# 7_VGA.net
KiCad netlist of a schematic drawn in Altium Designer
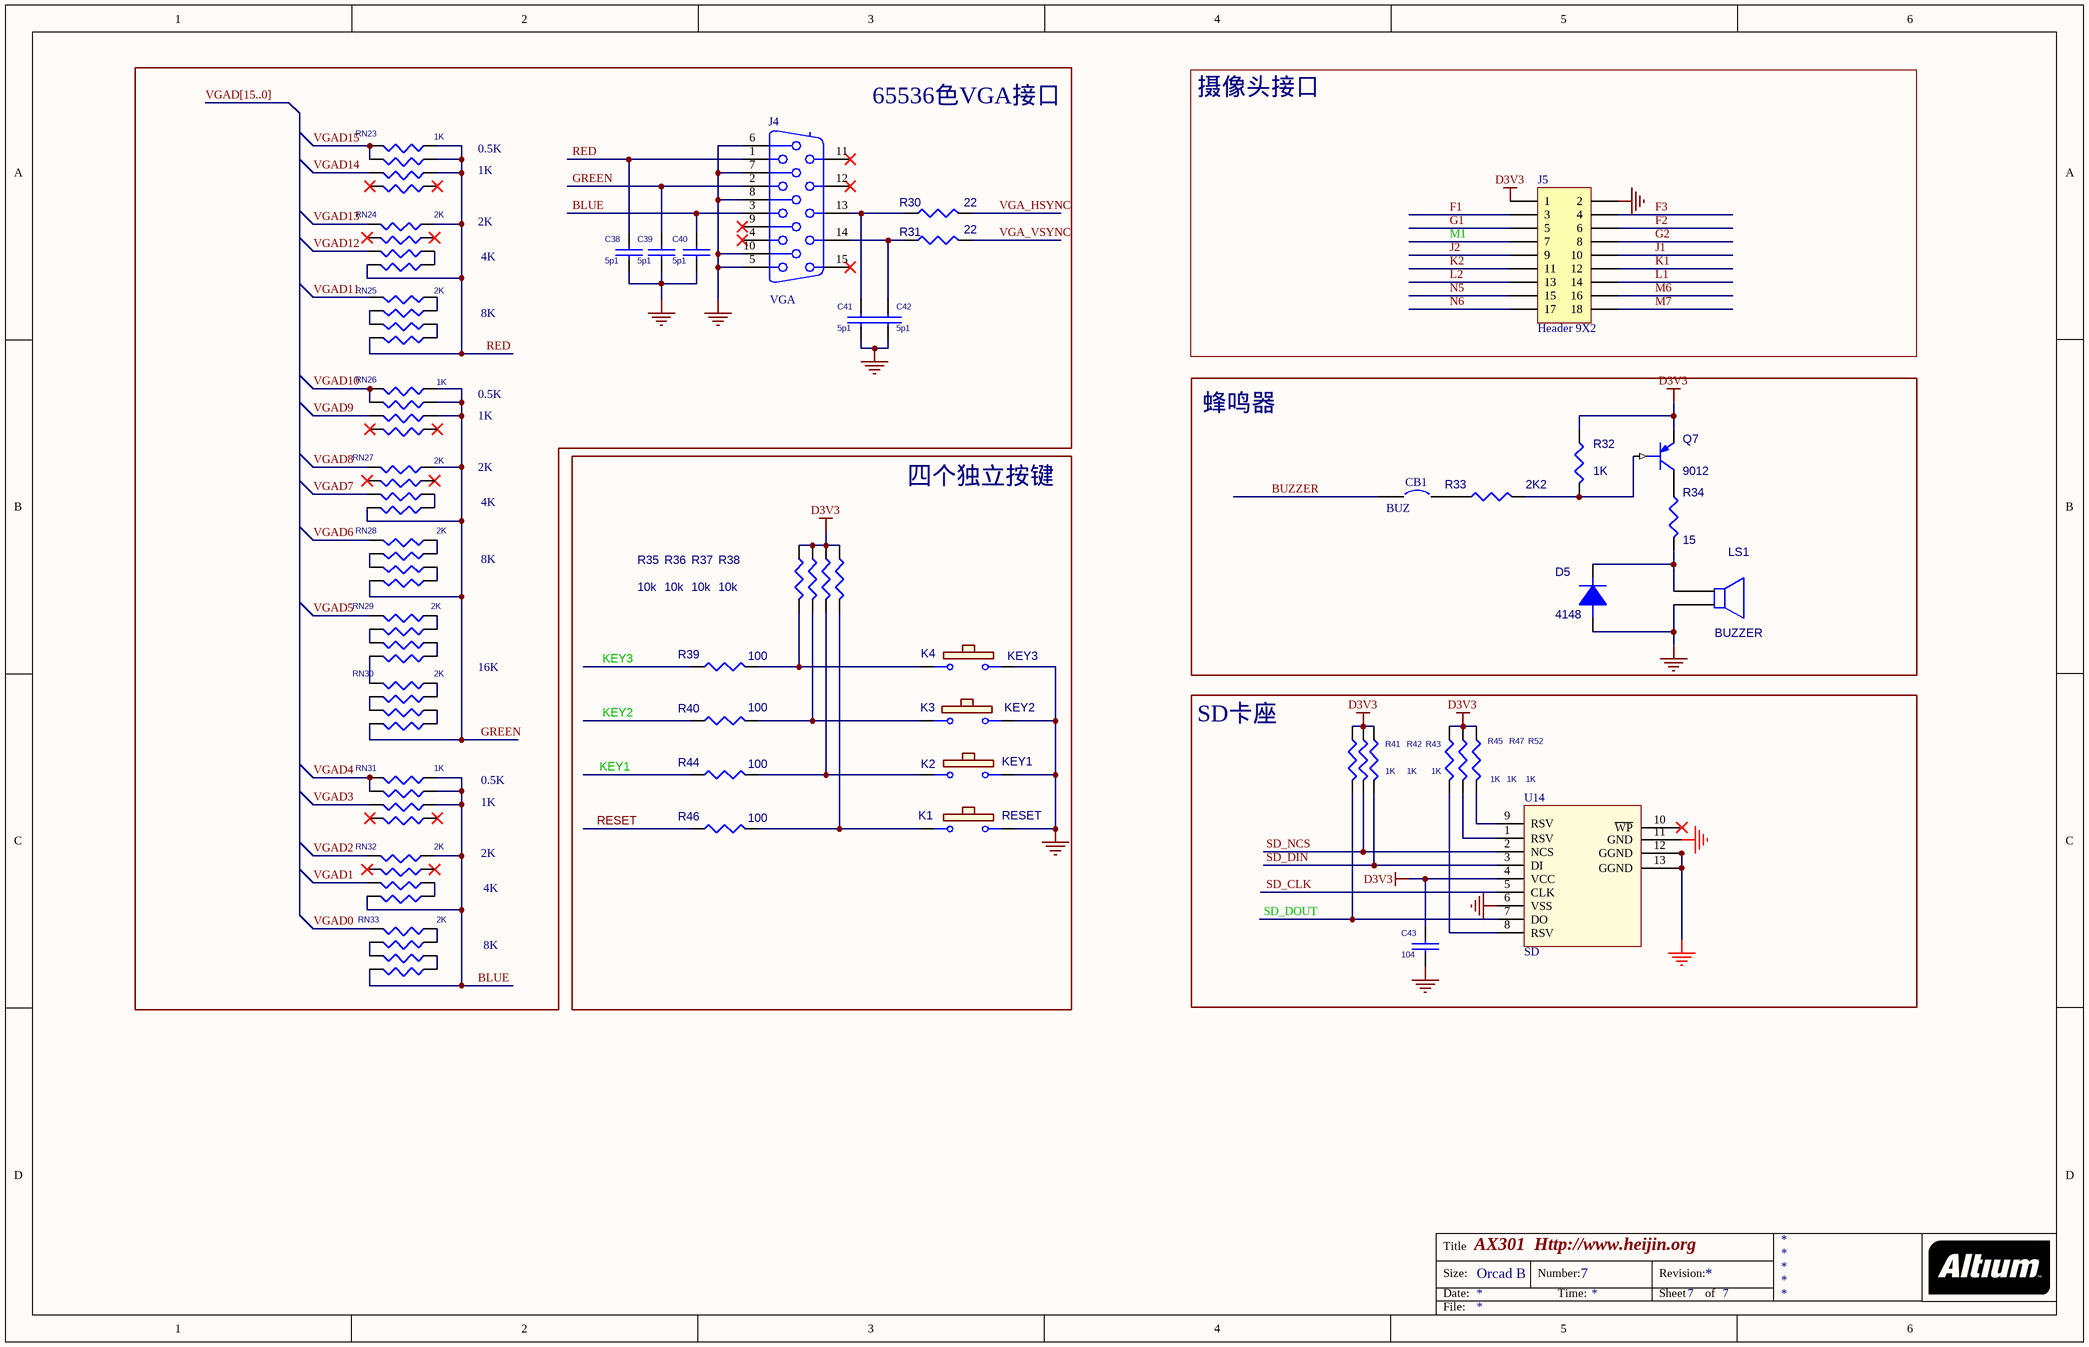
[diagram p0: 7_VGA.SchDoc]

(export (version "E")
  (design (tool "Eeschema 10.0.6"))
  (components
    (comp (ref "C38") (value "5p1") (footprint "0603") (libsource (lib "*") (part "C_Dup1")))
    (comp (ref "C39") (value "5p1") (footprint "0603") (libsource (lib "*") (part "C_Dup1")))
    (comp (ref "C40") (value "5p1") (footprint "0603") (libsource (lib "*") (part "C_Dup1")))
    (comp (ref "C41") (value "5p1") (footprint "0603") (libsource (lib "*") (part "C_Dup1")))
    (comp (ref "C42") (value "5p1") (footprint "0603") (libsource (lib "*") (part "C_Dup1")))
    (comp (ref "C43") (value "104") (footprint "0402") (libsource (lib "*") (part "C_Dup1")))
    (comp (ref "CB1")
      (value "BUZ")
      (footprint "SIP2")
      (description "Circuit Breaker")
      (fields (field (name "PUBLISHER") "Altium Limited"))
      (libsource (lib "Miscellaneous Devices") (part "Circuit Breaker"))
    )
    (comp (ref "D5") (value "4148") (libsource (lib "*") (part "4148")))
    (comp (ref "J4")
      (value "VGA")
      (footprint "wfj_pcb:VGA")
      (description "Receptacle Assembly, 15-Pin, Sim Line Connector")
      (fields (field (name "PUBLISHER") "Altium Limited"))
      (libsource (lib "Miscellaneous Connectors") (part "Connector 15"))
    )
    (comp (ref "J5")
      (value "Header 9X2")
      (footprint "HDR2X9")
      (description "Header, 9-Pin, Dual row")
      (fields (field (name "PUBLISHER") "Altium Limited"))
      (libsource (lib "Miscellaneous Connectors") (part "Header 9X2"))
    )
    (comp (ref "K1") (value "RESET") (footprint "KEY735SO") (libsource (lib "*") (part "KEYB")))
    (comp (ref "K2") (value "KEY1") (footprint "KEY735SO") (libsource (lib "*") (part "KEYB")))
    (comp (ref "K3") (value "KEY2") (footprint "KEY735SO") (libsource (lib "") (part "KEYB_1")))
    (comp (ref "K4") (value "KEY3") (footprint "KEY735SO") (libsource (lib "*") (part "KEYB")))
    (comp (ref "LS1") (value "BUZZER") (libsource (lib "*") (part "SPEAKER")))
    (comp (ref "Q7") (value "9012") (footprint "SOT23") (libsource (lib "*") (part "PNP")))
    (comp (ref "R30") (value "22") (footprint "0603") (libsource (lib "*") (part "R")))
    (comp (ref "R31") (value "22") (footprint "0603") (libsource (lib "*") (part "R")))
    (comp (ref "R32") (value "1K") (footprint "0603") (libsource (lib "*") (part "R_Dup3")))
    (comp (ref "R33") (value "2K2") (footprint "0603") (libsource (lib "*") (part "R_Dup3")))
    (comp (ref "R34") (value "15") (footprint "0603") (libsource (lib "*") (part "R_Dup3")))
    (comp (ref "R35") (value "10k") (footprint "0603") (libsource (lib "*") (part "R_Dup2")))
    (comp (ref "R36") (value "10k") (footprint "0603") (libsource (lib "*") (part "R_Dup2")))
    (comp (ref "R37") (value "10k") (footprint "0603") (libsource (lib "*") (part "R_Dup2")))
    (comp (ref "R38") (value "10k") (footprint "0603") (libsource (lib "*") (part "R_Dup2")))
    (comp (ref "R39") (value "100") (footprint "0603") (libsource (lib "*") (part "R_Dup2")))
    (comp (ref "R40") (value "100") (footprint "0603") (libsource (lib "*") (part "R_Dup2")))
    (comp (ref "R41") (value "1K") (footprint "0603") (libsource (lib "*") (part "R")))
    (comp (ref "R42") (value "1K") (footprint "0603") (libsource (lib "*") (part "R")))
    (comp (ref "R43") (value "1K") (footprint "0603") (libsource (lib "*") (part "R")))
    (comp (ref "R44") (value "100") (footprint "0603") (libsource (lib "*") (part "R_Dup2")))
    (comp (ref "R45") (value "1K") (footprint "0603") (libsource (lib "*") (part "R")))
    (comp (ref "R46") (value "100") (footprint "0603") (libsource (lib "*") (part "R_Dup2")))
    (comp (ref "R47") (value "1K") (footprint "0603") (libsource (lib "*") (part "R")))
    (comp (ref "R52") (value "1K") (footprint "0603") (libsource (lib "*") (part "R")))
    (comp (ref "RN23") (value "1K") (footprint "RN-8P") (libsource (lib "*") (part "RN_Dup1")))
    (comp (ref "RN24") (value "2K") (footprint "RN-8P") (libsource (lib "*") (part "RN_Dup1")))
    (comp (ref "RN25") (value "2K") (footprint "RN-8P") (libsource (lib "*") (part "RN_Dup1")))
    (comp (ref "RN26") (value "1K") (footprint "RN-8P") (libsource (lib "*") (part "RN_Dup1")))
    (comp (ref "RN27") (value "2K") (footprint "RN-8P") (libsource (lib "*") (part "RN_Dup1")))
    (comp (ref "RN28") (value "2K") (footprint "RN-8P") (libsource (lib "*") (part "RN_Dup1")))
    (comp (ref "RN29") (value "2K") (footprint "RN-8P") (libsource (lib "*") (part "RN_Dup1")))
    (comp (ref "RN30") (value "2K") (footprint "RN-8P") (libsource (lib "*") (part "RN_Dup1")))
    (comp (ref "RN31") (value "1K") (footprint "RN-8P") (libsource (lib "*") (part "RN_Dup1")))
    (comp (ref "RN32") (value "2K") (footprint "RN-8P") (libsource (lib "*") (part "RN_Dup1")))
    (comp (ref "RN33") (value "2K") (footprint "RN-8P") (libsource (lib "*") (part "RN_Dup1")))
    (comp (ref "U14") (value "SD") (footprint "TF") (libsource (lib "TFT") (part "SD")))
  )
  (nets
    (net (code "1") (name "/BLUE") (class "Default")
      (node (ref "C40") (pin "1") (pinfunction "1_1") (pintype "passive"))
      (node (ref "J4") (pin "3") (pinfunction "3_3") (pintype "passive"))
      (node (ref "RN31") (pin "2") (pinfunction "2_2") (pintype "passive"))
      (node (ref "RN31") (pin "3") (pinfunction "3_3") (pintype "passive"))
      (node (ref "RN31") (pin "4") (pinfunction "4_4") (pintype "passive"))
      (node (ref "RN32") (pin "4") (pinfunction "4_4") (pintype "passive"))
      (node (ref "RN32") (pin "8") (pinfunction "8_8") (pintype "passive"))
      (node (ref "RN33") (pin "8") (pinfunction "8_8") (pintype "passive"))
    )
    (net (code "2") (name "/BUZZER") (class "Default")
      (node (ref "CB1") (pin "1") (pinfunction "1_1") (pintype "passive"))
    )
    (net (code "3") (name "/F1") (class "Default")
      (node (ref "J5") (pin "3") (pinfunction "3_3") (pintype "passive"))
    )
    (net (code "4") (name "/F2") (class "Default")
      (node (ref "J5") (pin "6") (pinfunction "6_6") (pintype "passive"))
    )
    (net (code "5") (name "/F3") (class "Default")
      (node (ref "J5") (pin "4") (pinfunction "4_4") (pintype "passive"))
    )
    (net (code "6") (name "/G1") (class "Default")
      (node (ref "J5") (pin "5") (pinfunction "5_5") (pintype "passive"))
    )
    (net (code "7") (name "/G2") (class "Default")
      (node (ref "J5") (pin "8") (pinfunction "8_8") (pintype "passive"))
    )
    (net (code "8") (name "/GREEN") (class "Default")
      (node (ref "C39") (pin "1") (pinfunction "1_1") (pintype "passive"))
      (node (ref "J4") (pin "2") (pinfunction "2_2") (pintype "passive"))
      (node (ref "RN26") (pin "2") (pinfunction "2_2") (pintype "passive"))
      (node (ref "RN26") (pin "3") (pinfunction "3_3") (pintype "passive"))
      (node (ref "RN26") (pin "4") (pinfunction "4_4") (pintype "passive"))
      (node (ref "RN27") (pin "4") (pinfunction "4_4") (pintype "passive"))
      (node (ref "RN27") (pin "8") (pinfunction "8_8") (pintype "passive"))
      (node (ref "RN28") (pin "8") (pinfunction "8_8") (pintype "passive"))
      (node (ref "RN30") (pin "8") (pinfunction "8_8") (pintype "passive"))
    )
    (net (code "9") (name "/J1") (class "Default")
      (node (ref "J5") (pin "10") (pinfunction "10_10") (pintype "passive"))
    )
    (net (code "10") (name "/J2") (class "Default")
      (node (ref "J5") (pin "9") (pinfunction "9_9") (pintype "passive"))
    )
    (net (code "11") (name "/K1") (class "Default")
      (node (ref "J5") (pin "12") (pinfunction "12_12") (pintype "passive"))
    )
    (net (code "12") (name "/K2") (class "Default")
      (node (ref "J5") (pin "11") (pinfunction "11_11") (pintype "passive"))
    )
    (net (code "13") (name "/KEY1") (class "Default")
      (node (ref "R44") (pin "1") (pinfunction "1_1") (pintype "passive"))
    )
    (net (code "14") (name "/KEY2") (class "Default")
      (node (ref "R40") (pin "1") (pinfunction "1_1") (pintype "passive"))
    )
    (net (code "15") (name "/KEY3") (class "Default")
      (node (ref "R39") (pin "1") (pinfunction "1_1") (pintype "passive"))
    )
    (net (code "16") (name "/L1") (class "Default")
      (node (ref "J5") (pin "14") (pinfunction "14_14") (pintype "passive"))
    )
    (net (code "17") (name "/L2") (class "Default")
      (node (ref "J5") (pin "13") (pinfunction "13_13") (pintype "passive"))
    )
    (net (code "18") (name "/M1") (class "Default")
      (node (ref "J5") (pin "7") (pinfunction "7_7") (pintype "passive"))
    )
    (net (code "19") (name "/M6") (class "Default")
      (node (ref "J5") (pin "16") (pinfunction "16_16") (pintype "passive"))
    )
    (net (code "20") (name "/M7") (class "Default")
      (node (ref "J5") (pin "18") (pinfunction "18_18") (pintype "passive"))
    )
    (net (code "21") (name "/N5") (class "Default")
      (node (ref "J5") (pin "15") (pinfunction "15_15") (pintype "passive"))
    )
    (net (code "22") (name "/N6") (class "Default")
      (node (ref "J5") (pin "17") (pinfunction "17_17") (pintype "passive"))
    )
    (net (code "23") (name "/RED") (class "Default")
      (node (ref "C38") (pin "1") (pinfunction "1_1") (pintype "passive"))
      (node (ref "J4") (pin "1") (pinfunction "1_1") (pintype "passive"))
      (node (ref "RN23") (pin "2") (pinfunction "2_2") (pintype "passive"))
      (node (ref "RN23") (pin "3") (pinfunction "3_3") (pintype "passive"))
      (node (ref "RN23") (pin "4") (pinfunction "4_4") (pintype "passive"))
      (node (ref "RN24") (pin "4") (pinfunction "4_4") (pintype "passive"))
      (node (ref "RN24") (pin "8") (pinfunction "8_8") (pintype "passive"))
      (node (ref "RN25") (pin "8") (pinfunction "8_8") (pintype "passive"))
    )
    (net (code "24") (name "/RESET") (class "Default")
      (node (ref "R46") (pin "1") (pinfunction "1_1") (pintype "passive"))
    )
    (net (code "25") (name "/SD_CLK") (class "Default")
      (node (ref "U14") (pin "5") (pinfunction "CLK_5") (pintype "passive"))
    )
    (net (code "26") (name "/SD_DIN") (class "Default")
      (node (ref "R43") (pin "2") (pinfunction "2_2") (pintype "passive"))
      (node (ref "U14") (pin "3") (pinfunction "DI_3") (pintype "passive"))
    )
    (net (code "27") (name "/SD_DOUT") (class "Default")
      (node (ref "R41") (pin "2") (pinfunction "2_2") (pintype "passive"))
      (node (ref "U14") (pin "7") (pinfunction "DO_7") (pintype "passive"))
    )
    (net (code "28") (name "/SD_NCS") (class "Default")
      (node (ref "R42") (pin "2") (pinfunction "2_2") (pintype "passive"))
      (node (ref "U14") (pin "2") (pinfunction "NCS_2") (pintype "passive"))
    )
    (net (code "29") (name "/VGAD0") (class "Default")
      (node (ref "RN33") (pin "5") (pinfunction "5_5") (pintype "passive"))
    )
    (net (code "30") (name "/VGAD1") (class "Default")
      (node (ref "RN32") (pin "7") (pinfunction "7_7") (pintype "passive"))
    )
    (net (code "31") (name "/VGAD2") (class "Default")
      (node (ref "RN32") (pin "5") (pinfunction "5_5") (pintype "passive"))
    )
    (net (code "32") (name "/VGAD3") (class "Default")
      (node (ref "RN31") (pin "7") (pinfunction "7_7") (pintype "passive"))
    )
    (net (code "33") (name "/VGAD4") (class "Default")
      (node (ref "RN31") (pin "5") (pinfunction "5_5") (pintype "passive"))
      (node (ref "RN31") (pin "6") (pinfunction "6_6") (pintype "passive"))
    )
    (net (code "34") (name "/VGAD5") (class "Default")
      (node (ref "RN29") (pin "5") (pinfunction "5_5") (pintype "passive"))
    )
    (net (code "35") (name "/VGAD6") (class "Default")
      (node (ref "RN28") (pin "5") (pinfunction "5_5") (pintype "passive"))
    )
    (net (code "36") (name "/VGAD7") (class "Default")
      (node (ref "RN27") (pin "7") (pinfunction "7_7") (pintype "passive"))
    )
    (net (code "37") (name "/VGAD8") (class "Default")
      (node (ref "RN27") (pin "5") (pinfunction "5_5") (pintype "passive"))
    )
    (net (code "38") (name "/VGAD9") (class "Default")
      (node (ref "RN26") (pin "7") (pinfunction "7_7") (pintype "passive"))
    )
    (net (code "39") (name "/VGAD10") (class "Default")
      (node (ref "RN26") (pin "5") (pinfunction "5_5") (pintype "passive"))
      (node (ref "RN26") (pin "6") (pinfunction "6_6") (pintype "passive"))
    )
    (net (code "40") (name "/VGAD11") (class "Default")
      (node (ref "RN25") (pin "5") (pinfunction "5_5") (pintype "passive"))
    )
    (net (code "41") (name "/VGAD12") (class "Default")
      (node (ref "RN24") (pin "7") (pinfunction "7_7") (pintype "passive"))
    )
    (net (code "42") (name "/VGAD13") (class "Default")
      (node (ref "RN24") (pin "5") (pinfunction "5_5") (pintype "passive"))
    )
    (net (code "43") (name "/VGAD14") (class "Default")
      (node (ref "RN23") (pin "7") (pinfunction "7_7") (pintype "passive"))
    )
    (net (code "44") (name "/VGAD15") (class "Default")
      (node (ref "RN23") (pin "5") (pinfunction "5_5") (pintype "passive"))
      (node (ref "RN23") (pin "6") (pinfunction "6_6") (pintype "passive"))
    )
    (net (code "46") (name "/VGA_HSYNC") (class "Default")
      (node (ref "R30") (pin "2") (pinfunction "2_2") (pintype "passive"))
    )
    (net (code "47") (name "/VGA_VSYNC") (class "Default")
      (node (ref "R31") (pin "2") (pinfunction "2_2") (pintype "passive"))
    )
    (net (code "48") (name "D3V3") (class "Default")
      (node (ref "C43") (pin "1") (pinfunction "1_1") (pintype "passive"))
      (node (ref "J5") (pin "1") (pinfunction "1_1") (pintype "passive"))
      (node (ref "Q7") (pin "2") (pinfunction "EMITTER_2") (pintype "passive"))
      (node (ref "R32") (pin "1") (pinfunction "1_1") (pintype "passive"))
      (node (ref "R35") (pin "1") (pinfunction "1_1") (pintype "passive"))
      (node (ref "R36") (pin "1") (pinfunction "1_1") (pintype "passive"))
      (node (ref "R37") (pin "1") (pinfunction "1_1") (pintype "passive"))
      (node (ref "R38") (pin "1") (pinfunction "1_1") (pintype "passive"))
      (node (ref "R41") (pin "1") (pinfunction "1_1") (pintype "passive"))
      (node (ref "R42") (pin "1") (pinfunction "1_1") (pintype "passive"))
      (node (ref "R43") (pin "1") (pinfunction "1_1") (pintype "passive"))
      (node (ref "R45") (pin "1") (pinfunction "1_1") (pintype "passive"))
      (node (ref "R47") (pin "1") (pinfunction "1_1") (pintype "passive"))
      (node (ref "R52") (pin "1") (pinfunction "1_1") (pintype "passive"))
      (node (ref "U14") (pin "4") (pinfunction "VCC_4") (pintype "passive"))
    )
    (net (code "49") (name "GND") (class "Default")
      (node (ref "C38") (pin "2") (pinfunction "2_2") (pintype "passive"))
      (node (ref "C39") (pin "2") (pinfunction "2_2") (pintype "passive"))
      (node (ref "C40") (pin "2") (pinfunction "2_2") (pintype "passive"))
      (node (ref "C41") (pin "2") (pinfunction "2_2") (pintype "passive"))
      (node (ref "C42") (pin "2") (pinfunction "2_2") (pintype "passive"))
      (node (ref "C43") (pin "2") (pinfunction "2_2") (pintype "passive"))
      (node (ref "D5") (pin "1") (pinfunction "A_1") (pintype "passive"))
      (node (ref "J4") (pin "10") (pinfunction "10_10") (pintype "passive"))
      (node (ref "J4") (pin "5") (pinfunction "5_5") (pintype "passive"))
      (node (ref "J4") (pin "6") (pinfunction "6_6") (pintype "passive"))
      (node (ref "J4") (pin "7") (pinfunction "7_7") (pintype "passive"))
      (node (ref "J4") (pin "8") (pinfunction "8_8") (pintype "passive"))
      (node (ref "J5") (pin "2") (pinfunction "2_2") (pintype "passive"))
      (node (ref "K1") (pin "2") (pinfunction "2_2") (pintype "passive"))
      (node (ref "K2") (pin "2") (pinfunction "2_2") (pintype "passive"))
      (node (ref "K3") (pin "1") (pinfunction "1_1") (pintype "passive"))
      (node (ref "K4") (pin "2") (pinfunction "2_2") (pintype "passive"))
      (node (ref "LS1") (pin "2") (pinfunction "2_2") (pintype "passive"))
      (node (ref "U14") (pin "11") (pinfunction "GND_11") (pintype "passive"))
      (node (ref "U14") (pin "12") (pinfunction "GGND_12") (pintype "passive"))
      (node (ref "U14") (pin "13") (pinfunction "GGND_13") (pintype "passive"))
      (node (ref "U14") (pin "6") (pinfunction "VSS_6") (pintype "passive"))
    )
    (net (code "50") (name "Net-(C41-Pad1)") (class "Default")
      (node (ref "C41") (pin "1") (pinfunction "1_1") (pintype "passive"))
      (node (ref "J4") (pin "13") (pinfunction "13_13") (pintype "passive"))
      (node (ref "R30") (pin "1") (pinfunction "1_1") (pintype "passive"))
    )
    (net (code "51") (name "Net-(C42-Pad1)") (class "Default")
      (node (ref "C42") (pin "1") (pinfunction "1_1") (pintype "passive"))
      (node (ref "J4") (pin "14") (pinfunction "14_14") (pintype "passive"))
      (node (ref "R31") (pin "1") (pinfunction "1_1") (pintype "passive"))
    )
    (net (code "52") (name "Net-(CB1-Pad2)") (class "Default")
      (node (ref "CB1") (pin "2") (pinfunction "2_2") (pintype "passive"))
      (node (ref "R33") (pin "1") (pinfunction "1_1") (pintype "passive"))
    )
    (net (code "53") (name "Net-(D5-C)") (class "Default")
      (node (ref "D5") (pin "2") (pinfunction "C_2") (pintype "passive"))
      (node (ref "LS1") (pin "1") (pinfunction "1_1") (pintype "passive"))
      (node (ref "R34") (pin "2") (pinfunction "2_2") (pintype "passive"))
    )
    (net (code "54") (name "Net-(K1-Pad1)") (class "Default")
      (node (ref "K1") (pin "1") (pinfunction "1_1") (pintype "passive"))
      (node (ref "R38") (pin "2") (pinfunction "2_2") (pintype "passive"))
      (node (ref "R46") (pin "2") (pinfunction "2_2") (pintype "passive"))
    )
    (net (code "55") (name "Net-(K2-Pad1)") (class "Default")
      (node (ref "K2") (pin "1") (pinfunction "1_1") (pintype "passive"))
      (node (ref "R37") (pin "2") (pinfunction "2_2") (pintype "passive"))
      (node (ref "R44") (pin "2") (pinfunction "2_2") (pintype "passive"))
    )
    (net (code "56") (name "Net-(K3-Pad2)") (class "Default")
      (node (ref "K3") (pin "2") (pinfunction "2_2") (pintype "passive"))
      (node (ref "R36") (pin "2") (pinfunction "2_2") (pintype "passive"))
      (node (ref "R40") (pin "2") (pinfunction "2_2") (pintype "passive"))
    )
    (net (code "57") (name "Net-(K4-Pad1)") (class "Default")
      (node (ref "K4") (pin "1") (pinfunction "1_1") (pintype "passive"))
      (node (ref "R35") (pin "2") (pinfunction "2_2") (pintype "passive"))
      (node (ref "R39") (pin "2") (pinfunction "2_2") (pintype "passive"))
    )
    (net (code "58") (name "Net-(Q7-BASE)") (class "Default")
      (node (ref "Q7") (pin "1") (pinfunction "BASE_1") (pintype "input"))
      (node (ref "R32") (pin "2") (pinfunction "2_2") (pintype "passive"))
      (node (ref "R33") (pin "2") (pinfunction "2_2") (pintype "passive"))
    )
    (net (code "59") (name "Net-(Q7-COLLECTOR)") (class "Default")
      (node (ref "Q7") (pin "3") (pinfunction "COLLECTOR_3") (pintype "passive"))
      (node (ref "R34") (pin "1") (pinfunction "1_1") (pintype "passive"))
    )
    (net (code "60") (name "Net-(R45-Pad2)") (class "Default")
      (node (ref "R45") (pin "2") (pinfunction "2_2") (pintype "passive"))
      (node (ref "U14") (pin "8") (pinfunction "RSV_8") (pintype "passive"))
    )
    (net (code "61") (name "Net-(R47-Pad2)") (class "Default")
      (node (ref "R47") (pin "2") (pinfunction "2_2") (pintype "passive"))
      (node (ref "U14") (pin "1") (pinfunction "RSV_1") (pintype "passive"))
    )
    (net (code "62") (name "Net-(R52-Pad2)") (class "Default")
      (node (ref "R52") (pin "2") (pinfunction "2_2") (pintype "passive"))
      (node (ref "U14") (pin "9") (pinfunction "RSV_9") (pintype "passive"))
    )
    (net (code "63") (name "Net-(RN24-Pad1)") (class "Default")
      (node (ref "RN24") (pin "1") (pinfunction "1_1") (pintype "passive"))
      (node (ref "RN24") (pin "2") (pinfunction "2_2") (pintype "passive"))
    )
    (net (code "64") (name "Net-(RN25-Pad1)") (class "Default")
      (node (ref "RN25") (pin "1") (pinfunction "1_1") (pintype "passive"))
      (node (ref "RN25") (pin "2") (pinfunction "2_2") (pintype "passive"))
    )
    (net (code "65") (name "Net-(RN25-Pad3)") (class "Default")
      (node (ref "RN25") (pin "3") (pinfunction "3_3") (pintype "passive"))
      (node (ref "RN25") (pin "4") (pinfunction "4_4") (pintype "passive"))
    )
    (net (code "66") (name "Net-(RN25-Pad6)") (class "Default")
      (node (ref "RN25") (pin "6") (pinfunction "6_6") (pintype "passive"))
      (node (ref "RN25") (pin "7") (pinfunction "7_7") (pintype "passive"))
    )
    (net (code "67") (name "Net-(RN27-Pad1)") (class "Default")
      (node (ref "RN27") (pin "1") (pinfunction "1_1") (pintype "passive"))
      (node (ref "RN27") (pin "2") (pinfunction "2_2") (pintype "passive"))
    )
    (net (code "68") (name "Net-(RN28-Pad1)") (class "Default")
      (node (ref "RN28") (pin "1") (pinfunction "1_1") (pintype "passive"))
      (node (ref "RN28") (pin "2") (pinfunction "2_2") (pintype "passive"))
    )
    (net (code "69") (name "Net-(RN28-Pad3)") (class "Default")
      (node (ref "RN28") (pin "3") (pinfunction "3_3") (pintype "passive"))
      (node (ref "RN28") (pin "4") (pinfunction "4_4") (pintype "passive"))
    )
    (net (code "70") (name "Net-(RN28-Pad6)") (class "Default")
      (node (ref "RN28") (pin "6") (pinfunction "6_6") (pintype "passive"))
      (node (ref "RN28") (pin "7") (pinfunction "7_7") (pintype "passive"))
    )
    (net (code "71") (name "Net-(RN29-Pad1)") (class "Default")
      (node (ref "RN29") (pin "1") (pinfunction "1_1") (pintype "passive"))
      (node (ref "RN29") (pin "2") (pinfunction "2_2") (pintype "passive"))
    )
    (net (code "72") (name "Net-(RN29-Pad3)") (class "Default")
      (node (ref "RN29") (pin "3") (pinfunction "3_3") (pintype "passive"))
      (node (ref "RN29") (pin "4") (pinfunction "4_4") (pintype "passive"))
    )
    (net (code "73") (name "Net-(RN29-Pad6)") (class "Default")
      (node (ref "RN29") (pin "6") (pinfunction "6_6") (pintype "passive"))
      (node (ref "RN29") (pin "7") (pinfunction "7_7") (pintype "passive"))
    )
    (net (code "74") (name "Net-(RN29-Pad8)") (class "Default")
      (node (ref "RN29") (pin "8") (pinfunction "8_8") (pintype "passive"))
      (node (ref "RN30") (pin "5") (pinfunction "5_5") (pintype "passive"))
    )
    (net (code "75") (name "Net-(RN30-Pad1)") (class "Default")
      (node (ref "RN30") (pin "1") (pinfunction "1_1") (pintype "passive"))
      (node (ref "RN30") (pin "2") (pinfunction "2_2") (pintype "passive"))
    )
    (net (code "76") (name "Net-(RN30-Pad3)") (class "Default")
      (node (ref "RN30") (pin "3") (pinfunction "3_3") (pintype "passive"))
      (node (ref "RN30") (pin "4") (pinfunction "4_4") (pintype "passive"))
    )
    (net (code "77") (name "Net-(RN30-Pad6)") (class "Default")
      (node (ref "RN30") (pin "6") (pinfunction "6_6") (pintype "passive"))
      (node (ref "RN30") (pin "7") (pinfunction "7_7") (pintype "passive"))
    )
    (net (code "78") (name "Net-(RN32-Pad1)") (class "Default")
      (node (ref "RN32") (pin "1") (pinfunction "1_1") (pintype "passive"))
      (node (ref "RN32") (pin "2") (pinfunction "2_2") (pintype "passive"))
    )
    (net (code "79") (name "Net-(RN33-Pad1)") (class "Default")
      (node (ref "RN33") (pin "1") (pinfunction "1_1") (pintype "passive"))
      (node (ref "RN33") (pin "2") (pinfunction "2_2") (pintype "passive"))
    )
    (net (code "80") (name "Net-(RN33-Pad3)") (class "Default")
      (node (ref "RN33") (pin "3") (pinfunction "3_3") (pintype "passive"))
      (node (ref "RN33") (pin "4") (pinfunction "4_4") (pintype "passive"))
    )
    (net (code "81") (name "Net-(RN33-Pad6)") (class "Default")
      (node (ref "RN33") (pin "6") (pinfunction "6_6") (pintype "passive"))
      (node (ref "RN33") (pin "7") (pinfunction "7_7") (pintype "passive"))
    )
    (net (code "82") (name "unconnected-(J4-MH1-Pad16)") (class "Default")
      (node (ref "J4") (pin "16") (pinfunction "MH1_16") (pintype "passive"))
    )
    (net (code "83") (name "unconnected-(J4-MH2-Pad17)") (class "Default")
      (node (ref "J4") (pin "17") (pinfunction "MH2_17") (pintype "passive"))
    )
    (net (code "84") (name "unconnected-(J4-Pad4)") (class "Default")
      (node (ref "J4") (pin "4") (pinfunction "4_4") (pintype "passive+no_connect"))
    )
    (net (code "85") (name "unconnected-(J4-Pad9)") (class "Default")
      (node (ref "J4") (pin "9") (pinfunction "9_9") (pintype "passive+no_connect"))
    )
    (net (code "86") (name "unconnected-(J4-Pad11)") (class "Default")
      (node (ref "J4") (pin "11") (pinfunction "11_11") (pintype "passive+no_connect"))
    )
    (net (code "87") (name "unconnected-(J4-Pad12)") (class "Default")
      (node (ref "J4") (pin "12") (pinfunction "12_12") (pintype "passive+no_connect"))
    )
    (net (code "88") (name "unconnected-(J4-Pad15)") (class "Default")
      (node (ref "J4") (pin "15") (pinfunction "15_15") (pintype "passive+no_connect"))
    )
    (net (code "89") (name "unconnected-(RN23-Pad1)") (class "Default")
      (node (ref "RN23") (pin "1") (pinfunction "1_1") (pintype "passive+no_connect"))
    )
    (net (code "90") (name "unconnected-(RN23-Pad8)") (class "Default")
      (node (ref "RN23") (pin "8") (pinfunction "8_8") (pintype "passive+no_connect"))
    )
    (net (code "91") (name "unconnected-(RN24-Pad3)") (class "Default")
      (node (ref "RN24") (pin "3") (pinfunction "3_3") (pintype "passive+no_connect"))
    )
    (net (code "92") (name "unconnected-(RN24-Pad6)") (class "Default")
      (node (ref "RN24") (pin "6") (pinfunction "6_6") (pintype "passive+no_connect"))
    )
    (net (code "93") (name "unconnected-(RN26-Pad1)") (class "Default")
      (node (ref "RN26") (pin "1") (pinfunction "1_1") (pintype "passive+no_connect"))
    )
    (net (code "94") (name "unconnected-(RN26-Pad8)") (class "Default")
      (node (ref "RN26") (pin "8") (pinfunction "8_8") (pintype "passive+no_connect"))
    )
    (net (code "95") (name "unconnected-(RN27-Pad3)") (class "Default")
      (node (ref "RN27") (pin "3") (pinfunction "3_3") (pintype "passive+no_connect"))
    )
    (net (code "96") (name "unconnected-(RN27-Pad6)") (class "Default")
      (node (ref "RN27") (pin "6") (pinfunction "6_6") (pintype "passive+no_connect"))
    )
    (net (code "97") (name "unconnected-(RN31-Pad1)") (class "Default")
      (node (ref "RN31") (pin "1") (pinfunction "1_1") (pintype "passive+no_connect"))
    )
    (net (code "98") (name "unconnected-(RN31-Pad8)") (class "Default")
      (node (ref "RN31") (pin "8") (pinfunction "8_8") (pintype "passive+no_connect"))
    )
    (net (code "99") (name "unconnected-(RN32-Pad3)") (class "Default")
      (node (ref "RN32") (pin "3") (pinfunction "3_3") (pintype "passive+no_connect"))
    )
    (net (code "100") (name "unconnected-(RN32-Pad6)") (class "Default")
      (node (ref "RN32") (pin "6") (pinfunction "6_6") (pintype "passive+no_connect"))
    )
    (net (code "101") (name "unconnected-(U14-~{WP}-Pad10)") (class "Default")
      (node (ref "U14") (pin "10") (pinfunction "~{WP}_10") (pintype "passive+no_connect"))
    )
  )
)
